# x-IMU3-SA-Haptic.net
KiCad netlist of a schematic drawn in Altium Designer
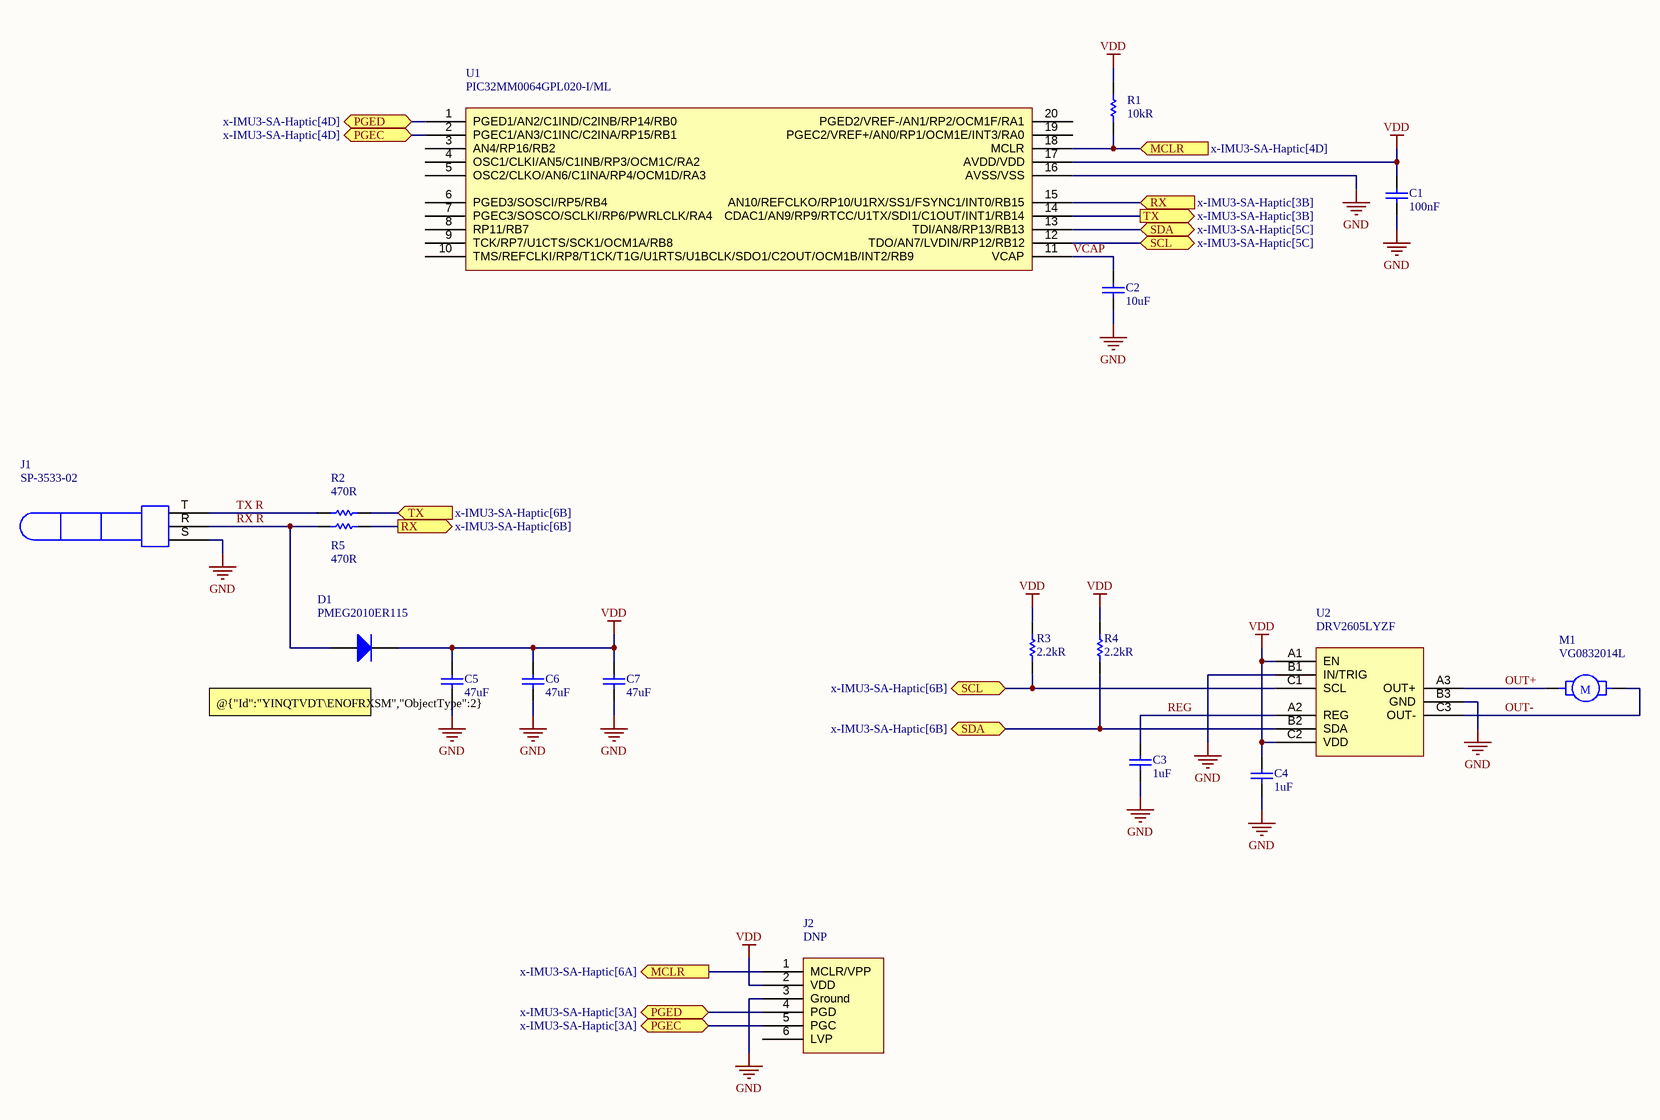
[diagram p0: x-IMU3-SA-Haptic.SchDoc]

(export (version "E")
  (design (tool "Eeschema 10.0.6"))
  (components
    (comp (ref "C1") (value "100nF") (footprint "Capacitor 0402") (libsource (lib "x-io") (part "Capacitor")))
    (comp (ref "C2") (value "10uF") (footprint "Capacitor 0402") (libsource (lib "x-io") (part "Capacitor")))
    (comp (ref "C3") (value "1uF") (footprint "Capacitor 0402") (libsource (lib "x-io") (part "Capacitor")))
    (comp (ref "C4") (value "1uF") (footprint "Capacitor 0402") (libsource (lib "x-io") (part "Capacitor")))
    (comp (ref "C5") (value "47uF") (footprint "Capacitor 0805") (libsource (lib "x-io") (part "Capacitor")))
    (comp (ref "C6") (value "47uF") (footprint "Capacitor 0805") (libsource (lib "x-io") (part "Capacitor")))
    (comp (ref "C7") (value "47uF") (footprint "Capacitor 0805") (libsource (lib "x-io") (part "Capacitor")))
    (comp (ref "D1") (value "PMEG2010ER115") (footprint "SOD-123") (libsource (lib "x-io") (part "Diode")))
    (comp (ref "J1")
      (value "SP-3533-02")
      (footprint "SP-3533-02")
      (libsource (lib "x-io") (part "SP-3533-02"))
    )
    (comp (ref "J2")
      (value "DNP")
      (footprint "Tag Connect No Legs")
      (libsource (lib "x-io") (part "MPLAB ICSP"))
    )
    (comp (ref "M1")
      (value "VG0832014L")
      (footprint "VG0832014L")
      (libsource (lib "x-io") (part "VG0832014L"))
    )
    (comp (ref "R1") (value "10kR") (footprint "Resistor 0402") (libsource (lib "x-io") (part "Resistor")))
    (comp (ref "R2") (value "470R") (footprint "Resistor 0402") (libsource (lib "x-io") (part "Resistor")))
    (comp (ref "R3") (value "2.2kR") (footprint "Resistor 0402") (libsource (lib "x-io") (part "Resistor")))
    (comp (ref "R4") (value "2.2kR") (footprint "Resistor 0402") (libsource (lib "x-io") (part "Resistor")))
    (comp (ref "R5") (value "470R") (footprint "Resistor 0402") (libsource (lib "x-io") (part "Resistor")))
    (comp (ref "U1")
      (value "PIC32MM0064GPL020-I/ML")
      (footprint "QFN-20")
      (libsource (lib "x-io") (part "PIC32MM0064GPL020-I/ML"))
    )
    (comp (ref "U2")
      (value "DRV2605LYZF")
      (footprint "DRV2605LYZF")
      (libsource (lib "x-io") (part "DRV2605LYZF"))
    )
  )
  (nets
    (net (code "1") (name "/MCLR") (class "Default")
      (node (ref "J2") (pin "1") (pinfunction "MCLR/VPP_1") (pintype "passive"))
      (node (ref "R1") (pin "1") (pinfunction "1_1") (pintype "passive"))
      (node (ref "U1") (pin "18") (pinfunction "MCLR_18") (pintype "passive"))
    )
    (net (code "2") (name "/OUT+") (class "Default")
      (node (ref "M1") (pin "2") (pinfunction "2_2") (pintype "passive"))
      (node (ref "U2") (pin "A3") (pinfunction "OUT+_A3") (pintype "passive"))
    )
    (net (code "3") (name "/OUT-") (class "Default")
      (node (ref "M1") (pin "1") (pinfunction "1_1") (pintype "passive"))
      (node (ref "U2") (pin "C3") (pinfunction "OUT-_C3") (pintype "passive"))
    )
    (net (code "4") (name "/PGEC") (class "Default")
      (node (ref "J2") (pin "5") (pinfunction "PGC_5") (pintype "passive"))
      (node (ref "U1") (pin "2") (pinfunction "PGEC1/AN3/C1INC/C2INA/RP15/RB1_2") (pintype "passive"))
    )
    (net (code "5") (name "/PGED") (class "Default")
      (node (ref "J2") (pin "4") (pinfunction "PGD_4") (pintype "passive"))
      (node (ref "U1") (pin "1") (pinfunction "PGED1/AN2/C1IND/C2INB/RP14/RB0_1") (pintype "passive"))
    )
    (net (code "6") (name "/REG") (class "Default")
      (node (ref "C3") (pin "2") (pinfunction "2_2") (pintype "passive"))
      (node (ref "U2") (pin "A2") (pinfunction "REG_A2") (pintype "passive"))
    )
    (net (code "7") (name "/RX") (class "Default")
      (node (ref "R5") (pin "2") (pinfunction "2_2") (pintype "passive"))
      (node (ref "U1") (pin "15") (pinfunction "AN10/REFCLKO/RP10/U1RX/SS1/FSYNC1/INT0/RB15_15") (pintype "passive"))
    )
    (net (code "8") (name "/RX R") (class "Default")
      (node (ref "D1") (pin "A") (pinfunction "A_A") (pintype "passive"))
      (node (ref "J1") (pin "R") (pinfunction "R_R") (pintype "passive"))
      (node (ref "R5") (pin "1") (pinfunction "1_1") (pintype "passive"))
    )
    (net (code "9") (name "/SCL") (class "Default")
      (node (ref "R3") (pin "1") (pinfunction "1_1") (pintype "passive"))
      (node (ref "U1") (pin "12") (pinfunction "TDO/AN7/LVDIN/RP12/RB12_12") (pintype "passive"))
      (node (ref "U2") (pin "C1") (pinfunction "SCL_C1") (pintype "passive"))
    )
    (net (code "10") (name "/SDA") (class "Default")
      (node (ref "R4") (pin "1") (pinfunction "1_1") (pintype "passive"))
      (node (ref "U1") (pin "13") (pinfunction "TDI/AN8/RP13/RB13_13") (pintype "passive"))
      (node (ref "U2") (pin "B2") (pinfunction "SDA_B2") (pintype "passive"))
    )
    (net (code "11") (name "/TX") (class "Default")
      (node (ref "R2") (pin "2") (pinfunction "2_2") (pintype "passive"))
      (node (ref "U1") (pin "14") (pinfunction "CDAC1/AN9/RP9/RTCC/U1TX/SDI1/C1OUT/INT1/RB14_14") (pintype "passive"))
    )
    (net (code "12") (name "/TX R") (class "Default")
      (node (ref "J1") (pin "T") (pinfunction "T_T") (pintype "passive"))
      (node (ref "R2") (pin "1") (pinfunction "1_1") (pintype "passive"))
    )
    (net (code "13") (name "/VCAP") (class "Default")
      (node (ref "C2") (pin "2") (pinfunction "2_2") (pintype "passive"))
      (node (ref "U1") (pin "11") (pinfunction "VCAP_11") (pintype "passive"))
    )
    (net (code "14") (name "GND") (class "Default")
      (node (ref "C1") (pin "1") (pinfunction "1_1") (pintype "passive"))
      (node (ref "C2") (pin "1") (pinfunction "1_1") (pintype "passive"))
      (node (ref "C3") (pin "1") (pinfunction "1_1") (pintype "passive"))
      (node (ref "C4") (pin "1") (pinfunction "1_1") (pintype "passive"))
      (node (ref "C5") (pin "1") (pinfunction "1_1") (pintype "passive"))
      (node (ref "C6") (pin "1") (pinfunction "1_1") (pintype "passive"))
      (node (ref "C7") (pin "1") (pinfunction "1_1") (pintype "passive"))
      (node (ref "J1") (pin "S") (pinfunction "S_S") (pintype "passive"))
      (node (ref "J2") (pin "3") (pinfunction "Ground_3") (pintype "passive"))
      (node (ref "U1") (pin "16") (pinfunction "AVSS/VSS_16") (pintype "passive"))
      (node (ref "U2") (pin "B1") (pinfunction "IN/TRIG_B1") (pintype "passive"))
      (node (ref "U2") (pin "B3") (pinfunction "GND_B3") (pintype "passive"))
    )
    (net (code "15") (name "VDD") (class "Default")
      (node (ref "C1") (pin "2") (pinfunction "2_2") (pintype "passive"))
      (node (ref "C4") (pin "2") (pinfunction "2_2") (pintype "passive"))
      (node (ref "C5") (pin "2") (pinfunction "2_2") (pintype "passive"))
      (node (ref "C6") (pin "2") (pinfunction "2_2") (pintype "passive"))
      (node (ref "C7") (pin "2") (pinfunction "2_2") (pintype "passive"))
      (node (ref "D1") (pin "K") (pinfunction "K_K") (pintype "passive"))
      (node (ref "J2") (pin "2") (pinfunction "VDD_2") (pintype "passive"))
      (node (ref "R1") (pin "2") (pinfunction "2_2") (pintype "passive"))
      (node (ref "R3") (pin "2") (pinfunction "2_2") (pintype "passive"))
      (node (ref "R4") (pin "2") (pinfunction "2_2") (pintype "passive"))
      (node (ref "U1") (pin "17") (pinfunction "AVDD/VDD_17") (pintype "passive"))
      (node (ref "U2") (pin "A1") (pinfunction "EN_A1") (pintype "passive"))
      (node (ref "U2") (pin "C2") (pinfunction "VDD_C2") (pintype "passive"))
    )
    (net (code "16") (name "unconnected-(J2-LVP-Pad6)") (class "Default")
      (node (ref "J2") (pin "6") (pinfunction "LVP_6") (pintype "passive"))
    )
    (net (code "17") (name "unconnected-(U1-AN4{slash}RP16{slash}RB2-Pad3)") (class "Default")
      (node (ref "U1") (pin "3") (pinfunction "AN4/RP16/RB2_3") (pintype "passive"))
    )
    (net (code "18") (name "unconnected-(U1-OSC1{slash}CLKI{slash}AN5{slash}C1INB{slash}RP3{slash}OCM1C{slash}RA2-Pad4)") (class "Default")
      (node (ref "U1") (pin "4") (pinfunction "OSC1/CLKI/AN5/C1INB/RP3/OCM1C/RA2_4") (pintype "passive"))
    )
    (net (code "19") (name "unconnected-(U1-OSC2{slash}CLKO{slash}AN6{slash}C1INA{slash}RP4{slash}OCM1D{slash}RA3-Pad5)") (class "Default")
      (node (ref "U1") (pin "5") (pinfunction "OSC2/CLKO/AN6/C1INA/RP4/OCM1D/RA3_5") (pintype "passive"))
    )
    (net (code "20") (name "unconnected-(U1-PGEC2{slash}VREF+{slash}AN0{slash}RP1{slash}OCM1E{slash}INT3{slash}RA0-Pad19)") (class "Default")
      (node (ref "U1") (pin "19") (pinfunction "PGEC2/VREF+/AN0/RP1/OCM1E/INT3/RA0_19") (pintype "passive"))
    )
    (net (code "21") (name "unconnected-(U1-PGEC3{slash}SOSCO{slash}SCLKI{slash}RP6{slash}PWRLCLK{slash}RA4-Pad7)") (class "Default")
      (node (ref "U1") (pin "7") (pinfunction "PGEC3/SOSCO/SCLKI/RP6/PWRLCLK/RA4_7") (pintype "passive"))
    )
    (net (code "22") (name "unconnected-(U1-PGED2{slash}VREF-{slash}AN1{slash}RP2{slash}OCM1F{slash}RA1-Pad20)") (class "Default")
      (node (ref "U1") (pin "20") (pinfunction "PGED2/VREF-/AN1/RP2/OCM1F/RA1_20") (pintype "passive"))
    )
    (net (code "23") (name "unconnected-(U1-PGED3{slash}SOSCI{slash}RP5{slash}RB4-Pad6)") (class "Default")
      (node (ref "U1") (pin "6") (pinfunction "PGED3/SOSCI/RP5/RB4_6") (pintype "passive"))
    )
    (net (code "24") (name "unconnected-(U1-RP11{slash}RB7-Pad8)") (class "Default")
      (node (ref "U1") (pin "8") (pinfunction "RP11/RB7_8") (pintype "passive"))
    )
    (net (code "25") (name "unconnected-(U1-TCK{slash}RP7{slash}U1CTS{slash}SCK1{slash}OCM1A{slash}RB8-Pad9)") (class "Default")
      (node (ref "U1") (pin "9") (pinfunction "TCK/RP7/U1CTS/SCK1/OCM1A/RB8_9") (pintype "passive"))
    )
    (net (code "26") (name "unconnected-(U1-TMS{slash}REFCLKI{slash}RP8{slash}T1CK{slash}T1G{slash}U1RTS{slash}U1BCLK{slash}SDO1{slash}C2OUT{slash}OCM1B{slash}INT2{slash}RB9-Pad10)") (class "Default")
      (node (ref "U1") (pin "10") (pinfunction "TMS/REFCLKI/RP8/T1CK/T1G/U1RTS/U1BCLK/SDO1/C2OUT/OCM1B/INT2/RB9_10") (pintype "passive"))
    )
  )
)
